# CoolantMonitor_MainBoard.net
KiCad netlist of a schematic drawn in Altium Designer
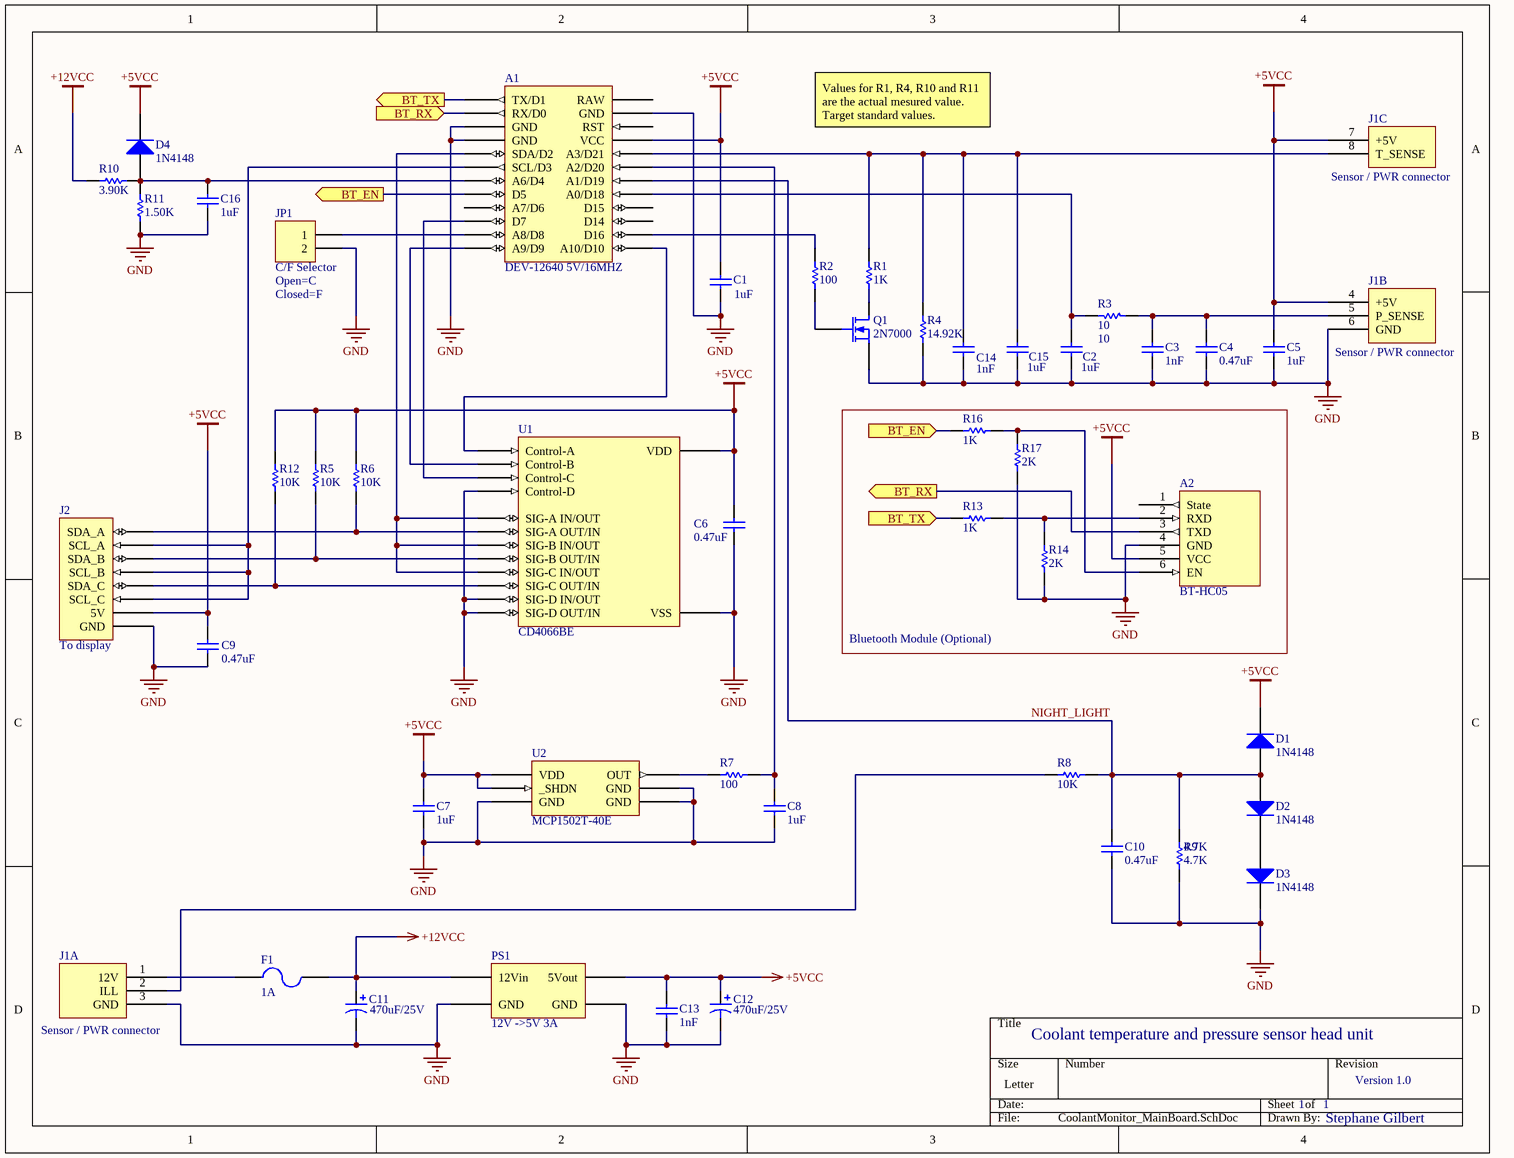
[diagram p0: CoolantMonitor_MainBoard.SchDoc]

(export (version "E")
  (design (tool "Eeschema 10.0.6"))
  (components
    (comp (ref "A1")
      (value "DEV-12640 5V/16MHZ")
      (footprint "ProMicro")
      (description "Arduino MCU")
      (fields (field (name "MANUFACTURER") "Sparkfun") (field (name "PART #") "DEV-12640"))
      (libsource (lib "CoolantMonitorLibrary") (part "ProMicro"))
    )
    (comp (ref "A2")
      (value "BT-HC05")
      (footprint "BT-HC05")
      (description "Bluetooth module")
      (fields (field (name "MANUFACTURER") "Many") (field (name "PART #") "HC-05"))
      (libsource (lib "CoolantMonitorLibrary") (part "BT-HC05"))
    )
    (comp (ref "C1")
      (value "1uF")
      (footprint "RAD_0.2_S")
      (description "Capacitor")
      (fields
        (field (name "MANUFACTURER") "TDK")
        (field (name "PART #") "FG28X7R1E105KRT06")
        (field (name "PUBLISHER") "Altium Limited")
      )
      (libsource (lib "Miscellaneous Devices") (part "Cap"))
    )
    (comp (ref "C2")
      (value "1uF")
      (footprint "RAD_0.2_S")
      (description "Capacitor")
      (fields
        (field (name "MANUFACTURER") "TDK")
        (field (name "PART #") "FG28X7R1E105KRT06")
        (field (name "PUBLISHER") "Altium Limited")
      )
      (libsource (lib "Miscellaneous Devices") (part "Cap"))
    )
    (comp (ref "C3")
      (value "1nF")
      (footprint "RAD_0.2_S")
      (description "Capacitor")
      (fields
        (field (name "MANUFACTURER") "Kemet")
        (field (name "PART #") "C315C102J3H5TA9170")
        (field (name "PUBLISHER") "Altium Limited")
      )
      (libsource (lib "Miscellaneous Devices") (part "Cap"))
    )
    (comp (ref "C4")
      (value "0.47uF")
      (footprint "RAD_0.2_S")
      (description "Capacitor")
      (fields
        (field (name "MANUFACTURER") "TDK")
        (field (name "PART #") "FA24X7R1E474KNU06")
        (field (name "PUBLISHER") "Altium Limited")
      )
      (libsource (lib "Miscellaneous Devices") (part "Cap"))
    )
    (comp (ref "C5")
      (value "1uF")
      (footprint "RAD_0.2_S")
      (description "Capacitor")
      (fields
        (field (name "MANUFACTURER") "TDK")
        (field (name "PART #") "FG28X7R1E105KRT06")
        (field (name "PUBLISHER") "Altium Limited")
      )
      (libsource (lib "Miscellaneous Devices") (part "Cap"))
    )
    (comp (ref "C6")
      (value "0.47uF")
      (footprint "RAD_0.2_S")
      (description "Capacitor")
      (fields
        (field (name "MANUFACTURER") "TDK")
        (field (name "PART #") "FA24X7R1E474KNU06")
        (field (name "PUBLISHER") "Altium Limited")
      )
      (libsource (lib "Miscellaneous Devices") (part "Cap"))
    )
    (comp (ref "C7")
      (value "1uF")
      (footprint "RAD_0.2_S")
      (description "Capacitor")
      (fields
        (field (name "MANUFACTURER") "TDK")
        (field (name "PART #") "FG28X7R1E105KRT06")
        (field (name "PUBLISHER") "Altium Limited")
      )
      (libsource (lib "Miscellaneous Devices") (part "Cap"))
    )
    (comp (ref "C8")
      (value "1uF")
      (footprint "RAD_0.2_S")
      (description "Capacitor")
      (fields
        (field (name "MANUFACTURER") "TDK")
        (field (name "PART #") "FG28X7R1E105KRT06")
        (field (name "PUBLISHER") "Altium Limited")
      )
      (libsource (lib "Miscellaneous Devices") (part "Cap"))
    )
    (comp (ref "C9")
      (value "0.47uF")
      (footprint "RAD_0.2_S")
      (description "Capacitor")
      (fields
        (field (name "MANUFACTURER") "TDK")
        (field (name "PART #") "FA24X7R1E474KNU06")
        (field (name "PUBLISHER") "Altium Limited")
      )
      (libsource (lib "Miscellaneous Devices") (part "Cap"))
    )
    (comp (ref "C10")
      (value "0.47uF")
      (footprint "RAD_0.2_S")
      (description "Capacitor")
      (fields
        (field (name "MANUFACTURER") "TDK")
        (field (name "PART #") "FA24X7R1E474KNU06")
        (field (name "PUBLISHER") "Altium Limited")
      )
      (libsource (lib "Miscellaneous Devices") (part "Cap"))
    )
    (comp (ref "C11")
      (value "470uF/25V")
      (footprint "RB_3.5MM")
      (description "Polarized Capacitor (Radial)")
      (fields
        (field (name "MANUFACTURER") "Vishay")
        (field (name "PART #") "MAL214656471E3")
        (field (name "PUBLISHER") "Altium Limited")
      )
      (libsource (lib "Miscellaneous Devices") (part "Cap Pol1"))
    )
    (comp (ref "C12")
      (value "470uF/25V")
      (footprint "RB_3.5MM")
      (description "Polarized Capacitor (Radial)")
      (fields
        (field (name "MANUFACTURER") "Vishay")
        (field (name "PART #") "MAL214656471E3")
        (field (name "PUBLISHER") "Altium Limited")
      )
      (libsource (lib "Miscellaneous Devices") (part "Cap Pol1"))
    )
    (comp (ref "C13")
      (value "1nF")
      (footprint "RAD_0.2_S")
      (description "Capacitor")
      (fields
        (field (name "MANUFACTURER") "Kemet")
        (field (name "PART #") "C315C102J3H5TA9170")
        (field (name "PUBLISHER") "Altium Limited")
      )
      (libsource (lib "Miscellaneous Devices") (part "Cap"))
    )
    (comp (ref "C14")
      (value "1nF")
      (footprint "RAD_0.2_S")
      (description "Capacitor")
      (fields
        (field (name "MANUFACTURER") "Kemet")
        (field (name "PART #") "C315C102J3H5TA9170")
        (field (name "PUBLISHER") "Altium Limited")
      )
      (libsource (lib "Miscellaneous Devices") (part "Cap"))
    )
    (comp (ref "C15")
      (value "1uF")
      (footprint "RAD_0.2_S")
      (description "Capacitor")
      (fields
        (field (name "MANUFACTURER") "TDK")
        (field (name "PART #") "FG28X7R1E105KRT06")
        (field (name "PUBLISHER") "Altium Limited")
      )
      (libsource (lib "Miscellaneous Devices") (part "Cap"))
    )
    (comp (ref "C16")
      (value "1uF")
      (footprint "RAD_0.2_S")
      (description "Capacitor")
      (fields
        (field (name "MANUFACTURER") "TDK")
        (field (name "PART #") "FG28X7R1E105KRT06")
        (field (name "PUBLISHER") "Altium Limited")
      )
      (libsource (lib "Miscellaneous Devices") (part "Cap"))
    )
    (comp (ref "D1")
      (value "1N4148")
      (footprint "DO-35A")
      (description "High Conductance Fast Diode")
      (fields (field (name "MANUFACTURER") "Onsemi") (field (name "PUBLISHER") "Altium Limited"))
      (libsource (lib "Miscellaneous Devices") (part "Diode 1N4148"))
    )
    (comp (ref "D2")
      (value "1N4148")
      (footprint "DO-35A")
      (description "High Conductance Fast Diode")
      (fields (field (name "MANUFACTURER") "Onsemi") (field (name "PUBLISHER") "Altium Limited"))
      (libsource (lib "Miscellaneous Devices") (part "Diode 1N4148"))
    )
    (comp (ref "D3")
      (value "1N4148")
      (footprint "DO-35A")
      (description "High Conductance Fast Diode")
      (fields (field (name "MANUFACTURER") "Onsemi") (field (name "PUBLISHER") "Altium Limited"))
      (libsource (lib "Miscellaneous Devices") (part "Diode 1N4148"))
    )
    (comp (ref "D4")
      (value "1N4148")
      (footprint "DO-35A")
      (description "High Conductance Fast Diode")
      (fields (field (name "MANUFACTURER") "Onsemi") (field (name "PUBLISHER") "Altium Limited"))
      (libsource (lib "Miscellaneous Devices") (part "Diode 1N4148"))
    )
    (comp (ref "F1")
      (value "1A")
      (footprint "AXIAL-0.4")
      (description "Fuse")
      (fields
        (field (name "MANUFACTURER") "Littlefuse")
        (field (name "PART #") "0251.500NRT1L")
        (field (name "PUBLISHER") "Altium Limited")
      )
      (libsource (lib "Miscellaneous Devices") (part "Fuse 2"))
    )
    (comp (ref "J1")
      (value "Sensor / PWR connector")
      (footprint "MTA-100-8")
      (description "8 Pins connector")
      (fields (field (name "MANUFACTURER") "Molex") (field (name "PART #") "1723162108"))
      (libsource (lib "CoolantMonitorLibrary") (part "SENS_INTERFACE_RX8"))
    )
    (comp (ref "J2")
      (value "To display")
      (footprint "MOLEX_ULTRA_FIT_8_POS_RA")
      (description "8 Pins connector")
      (fields (field (name "MANUFACTURER") "Molex") (field (name "PART #") "1723162108"))
      (libsource (lib "CoolantMonitorLibrary") (part "TRIPLE_DISPLAY_RX8"))
    )
    (comp (ref "JP1")
      (value "C/F Selector")
      (footprint "HDR1X2")
      (description "Header, 2-Pin")
      (fields (field (name "PUBLISHER") "Altium Limited"))
      (libsource (lib "Miscellaneous Connectors") (part "Header 2"))
    )
    (comp (ref "PS1")
      (value "12V ->5V 3A")
      (footprint "CPT_DC-DC")
      (description "CPT DC-DC 12V/5V 3A")
      (fields (field (name "MANUFACTURER") "Car Power Technology"))
      (libsource (lib "CoolantMonitorLibrary") (part "CPT_DC-DC"))
    )
    (comp (ref "Q1")
      (value "2N7000")
      (footprint "TO-92A")
      (description "N-Channel MOSFET")
      (fields (field (name "MANUFACTURER") "STMicroelectronics") (field (name "PUBLISHER") "Altium Limited"))
      (libsource (lib "Miscellaneous Devices") (part "MOSFET-N"))
    )
    (comp (ref "R1")
      (value "1K")
      (footprint "AXIAL-0.4")
      (description "Resistor")
      (fields
        (field (name "MANUFACTURER") "Stackpole Electronics Inc")
        (field (name "PART #") "CF18JT1K00")
        (field (name "PUBLISHER") "Altium Limited")
      )
      (libsource (lib "Miscellaneous Devices") (part "Res1"))
    )
    (comp (ref "R2")
      (value "100")
      (footprint "AXIAL-0.4")
      (description "Resistor")
      (fields
        (field (name "MANUFACTURER") "Stackpole Electronics Inc")
        (field (name "PART #") "CF18JT100R")
        (field (name "PUBLISHER") "Altium Limited")
      )
      (libsource (lib "Miscellaneous Devices") (part "Res1"))
    )
    (comp (ref "R3")
      (value "10")
      (footprint "AXIAL-0.4")
      (description "Resistor")
      (fields
        (field (name "ALTIUM_VALUE") "10")
        (field (name "MANUFACTURER") "Stackpole Electronics Inc")
        (field (name "PART #") "CF18JT10R0")
        (field (name "PUBLISHER") "Altium Limited")
      )
      (libsource (lib "Miscellaneous Devices") (part "Res1"))
    )
    (comp (ref "R4")
      (value "14.92K")
      (footprint "AXIAL-0.4")
      (description "Resistor")
      (fields
        (field (name "MANUFACTURER") "Stackpole Electronics Inc")
        (field (name "PART #") "CF18JT15K0")
        (field (name "PUBLISHER") "Altium Limited")
      )
      (libsource (lib "Miscellaneous Devices") (part "Res1"))
    )
    (comp (ref "R5")
      (value "10K")
      (footprint "AXIAL-0.4")
      (description "Resistor")
      (fields
        (field (name "MANUFACTURER") "Stackpole Electronics Inc")
        (field (name "PART #") "CF18JT10K0")
        (field (name "PUBLISHER") "Altium Limited")
      )
      (libsource (lib "Miscellaneous Devices") (part "Res1"))
    )
    (comp (ref "R6")
      (value "10K")
      (footprint "AXIAL-0.4")
      (description "Resistor")
      (fields
        (field (name "MANUFACTURER") "Stackpole Electronics Inc")
        (field (name "PART #") "CF18JT10K0")
        (field (name "PUBLISHER") "Altium Limited")
      )
      (libsource (lib "Miscellaneous Devices") (part "Res1"))
    )
    (comp (ref "R7")
      (value "100")
      (footprint "AXIAL-0.4")
      (description "Resistor")
      (fields
        (field (name "MANUFACTURER") "Stackpole Electronics Inc")
        (field (name "PART #") "CF18JT100R")
        (field (name "PUBLISHER") "Altium Limited")
      )
      (libsource (lib "Miscellaneous Devices") (part "Res1"))
    )
    (comp (ref "R8")
      (value "10K")
      (footprint "AXIAL-0.4")
      (description "Resistor")
      (fields
        (field (name "MANUFACTURER") "Stackpole Electronics Inc")
        (field (name "PART #") "CF18JT10K0")
        (field (name "PUBLISHER") "Altium Limited")
      )
      (libsource (lib "Miscellaneous Devices") (part "Res1"))
    )
    (comp (ref "R9")
      (value "4.7K")
      (footprint "AXIAL-0.4")
      (description "Resistor")
      (fields
        (field (name "ALTIUM_VALUE") "4.7K")
        (field (name "MANUFACTURER") "Stackpole Electronics Inc")
        (field (name "PART #") "CF18JT4K70")
        (field (name "PUBLISHER") "Altium Limited")
      )
      (libsource (lib "Miscellaneous Devices") (part "Res1"))
    )
    (comp (ref "R10")
      (value "3.90K")
      (footprint "AXIAL-0.4")
      (description "Resistor")
      (fields
        (field (name "MANUFACTURER") "Stackpole Electronics Inc")
        (field (name "PART #") "CF18JT3K90")
        (field (name "PUBLISHER") "Altium Limited")
      )
      (libsource (lib "Miscellaneous Devices") (part "Res1"))
    )
    (comp (ref "R11")
      (value "1.50K")
      (footprint "AXIAL-0.4")
      (description "Resistor")
      (fields
        (field (name "MANUFACTURER") "Stackpole Electronics Inc")
        (field (name "PART #") "CF18JT1K50")
        (field (name "PUBLISHER") "Altium Limited")
      )
      (libsource (lib "Miscellaneous Devices") (part "Res1"))
    )
    (comp (ref "R12")
      (value "10K")
      (footprint "AXIAL-0.4")
      (description "Resistor")
      (fields
        (field (name "MANUFACTURER") "Stackpole Electronics Inc")
        (field (name "PART #") "CF18JT10K0")
        (field (name "PUBLISHER") "Altium Limited")
      )
      (libsource (lib "Miscellaneous Devices") (part "Res1"))
    )
    (comp (ref "R13")
      (value "1K")
      (footprint "AXIAL-0.4")
      (description "Resistor")
      (fields
        (field (name "MANUFACTURER") "Stackpole Electronics Inc")
        (field (name "PART #") "CF18JT1K00")
        (field (name "PUBLISHER") "Altium Limited")
      )
      (libsource (lib "Miscellaneous Devices") (part "Res1"))
    )
    (comp (ref "R14")
      (value "2K")
      (footprint "AXIAL-0.4")
      (description "Resistor")
      (fields
        (field (name "MANUFACTURER") "Stackpole Electronics Inc")
        (field (name "PART #") "CF18JT2K00")
        (field (name "PUBLISHER") "Altium Limited")
      )
      (libsource (lib "Miscellaneous Devices") (part "Res1"))
    )
    (comp (ref "R16")
      (value "1K")
      (footprint "AXIAL-0.4")
      (description "Resistor")
      (fields
        (field (name "MANUFACTURER") "Stackpole Electronics Inc")
        (field (name "PART #") "CF18JT1K00")
        (field (name "PUBLISHER") "Altium Limited")
      )
      (libsource (lib "Miscellaneous Devices") (part "Res1"))
    )
    (comp (ref "R17")
      (value "2K")
      (footprint "AXIAL-0.4")
      (description "Resistor")
      (fields
        (field (name "MANUFACTURER") "Stackpole Electronics Inc")
        (field (name "PART #") "CF18JT2K00")
        (field (name "PUBLISHER") "Altium Limited")
      )
      (libsource (lib "Miscellaneous Devices") (part "Res1"))
    )
    (comp (ref "U1")
      (value "CD4066BE")
      (footprint "DIP-14")
      (description "Quad bilateral switch")
      (fields (field (name "MANUFACTURER") "TI"))
      (libsource (lib "CoolantMonitorLibrary") (part "CD4066BE"))
    )
    (comp (ref "U2")
      (value "MCP1502T-40E")
      (footprint "SOT-6-S")
      (description "Voltage reference")
      (fields (field (name "MANUFACTURER") "Michochip") (field (name "PART #") "MCP1502T-40E/CHY"))
      (libsource (lib "CoolantMonitorLibrary") (part "MCP1502"))
    )
  )
  (nets
    (net (code "1") (name "+5VCC") (class "Default")
      (node (ref "A1") (pin "21") (pinfunction "VCC_21") (pintype "power_in"))
      (node (ref "A2") (pin "5") (pinfunction "VCC_5") (pintype "power_in"))
      (node (ref "C1") (pin "2") (pinfunction "2_2") (pintype "passive"))
      (node (ref "C12") (pin "1") (pinfunction "1_1") (pintype "passive"))
      (node (ref "C13") (pin "2") (pinfunction "2_2") (pintype "passive"))
      (node (ref "C5") (pin "2") (pinfunction "2_2") (pintype "passive"))
      (node (ref "C6") (pin "2") (pinfunction "2_2") (pintype "passive"))
      (node (ref "C7") (pin "2") (pinfunction "2_2") (pintype "passive"))
      (node (ref "C9") (pin "2") (pinfunction "2_2") (pintype "passive"))
      (node (ref "D1") (pin "2") (pinfunction "K_2") (pintype "passive"))
      (node (ref "D4") (pin "2") (pinfunction "K_2") (pintype "passive"))
      (node (ref "J1") (pin "4") (pinfunction "+5V_4") (pintype "power_in"))
      (node (ref "J1") (pin "7") (pinfunction "+5V_7") (pintype "power_in"))
      (node (ref "J2") (pin "1") (pinfunction "5V_1") (pintype "power_in"))
      (node (ref "PS1") (pin "3") (pinfunction "5Vout_3") (pintype "power_in"))
      (node (ref "R12") (pin "2") (pinfunction "2_2") (pintype "passive"))
      (node (ref "R5") (pin "2") (pinfunction "2_2") (pintype "passive"))
      (node (ref "R6") (pin "2") (pinfunction "2_2") (pintype "passive"))
      (node (ref "U1") (pin "14") (pinfunction "VDD_14") (pintype "power_in"))
      (node (ref "U2") (pin "4") (pinfunction "_SHDN_4") (pintype "input"))
      (node (ref "U2") (pin "6") (pinfunction "VDD_6") (pintype "power_in"))
    )
    (net (code "2") (name "+12VCC") (class "Default")
      (node (ref "C11") (pin "1") (pinfunction "1_1") (pintype "passive"))
      (node (ref "F1") (pin "2") (pinfunction "2_2") (pintype "passive"))
      (node (ref "PS1") (pin "2") (pinfunction "12Vin_2") (pintype "power_in"))
      (node (ref "R10") (pin "1") (pinfunction "1_1") (pintype "passive"))
    )
    (net (code "3") (name "/BT_EN") (class "Default")
      (node (ref "A1") (pin "8") (pinfunction "D5_8") (pintype "bidirectional"))
      (node (ref "R16") (pin "2") (pinfunction "2_2") (pintype "passive"))
    )
    (net (code "4") (name "/BT_RX") (class "Default")
      (node (ref "A1") (pin "2") (pinfunction "RX/D0_2") (pintype "output"))
      (node (ref "A2") (pin "3") (pinfunction "TXD_3") (pintype "output"))
    )
    (net (code "5") (name "/BT_TX") (class "Default")
      (node (ref "A1") (pin "1") (pinfunction "TX/D1_1") (pintype "output"))
      (node (ref "R13") (pin "2") (pinfunction "2_2") (pintype "passive"))
    )
    (net (code "6") (name "/NIGHT_LIGHT") (class "Default")
      (node (ref "A1") (pin "18") (pinfunction "A1/D19_18") (pintype "input"))
      (node (ref "C10") (pin "2") (pinfunction "2_2") (pintype "passive"))
      (node (ref "D1") (pin "1") (pinfunction "A_1") (pintype "passive"))
      (node (ref "D2") (pin "1") (pinfunction "A_1") (pintype "passive"))
      (node (ref "R8") (pin "2") (pinfunction "2_2") (pintype "passive"))
      (node (ref "R9") (pin "2") (pinfunction "2_2") (pintype "passive"))
    )
    (net (code "7") (name "GND") (class "Default")
      (node (ref "A1") (pin "23") (pinfunction "GND_23") (pintype "power_in"))
      (node (ref "A1") (pin "3") (pinfunction "GND_3") (pintype "power_in"))
      (node (ref "A1") (pin "4") (pinfunction "GND_4") (pintype "power_in"))
      (node (ref "A2") (pin "4") (pinfunction "GND_4") (pintype "power_in"))
      (node (ref "C1") (pin "1") (pinfunction "1_1") (pintype "passive"))
      (node (ref "C10") (pin "1") (pinfunction "1_1") (pintype "passive"))
      (node (ref "C11") (pin "2") (pinfunction "2_2") (pintype "passive"))
      (node (ref "C12") (pin "2") (pinfunction "2_2") (pintype "passive"))
      (node (ref "C13") (pin "1") (pinfunction "1_1") (pintype "passive"))
      (node (ref "C14") (pin "1") (pinfunction "1_1") (pintype "passive"))
      (node (ref "C15") (pin "1") (pinfunction "1_1") (pintype "passive"))
      (node (ref "C16") (pin "1") (pinfunction "1_1") (pintype "passive"))
      (node (ref "C2") (pin "1") (pinfunction "1_1") (pintype "passive"))
      (node (ref "C3") (pin "1") (pinfunction "1_1") (pintype "passive"))
      (node (ref "C4") (pin "1") (pinfunction "1_1") (pintype "passive"))
      (node (ref "C5") (pin "1") (pinfunction "1_1") (pintype "passive"))
      (node (ref "C6") (pin "1") (pinfunction "1_1") (pintype "passive"))
      (node (ref "C7") (pin "1") (pinfunction "1_1") (pintype "passive"))
      (node (ref "C8") (pin "1") (pinfunction "1_1") (pintype "passive"))
      (node (ref "C9") (pin "1") (pinfunction "1_1") (pintype "passive"))
      (node (ref "D3") (pin "2") (pinfunction "K_2") (pintype "passive"))
      (node (ref "J1") (pin "3") (pinfunction "GND_3") (pintype "power_in"))
      (node (ref "J1") (pin "6") (pinfunction "GND_6") (pintype "power_in"))
      (node (ref "J2") (pin "2") (pinfunction "GND_2") (pintype "power_in"))
      (node (ref "JP1") (pin "2") (pinfunction "2_2") (pintype "passive"))
      (node (ref "PS1") (pin "1") (pinfunction "GND_1") (pintype "power_in"))
      (node (ref "PS1") (pin "4") (pinfunction "GND_4") (pintype "power_in"))
      (node (ref "Q1") (pin "3") (pinfunction "S_3") (pintype "passive"))
      (node (ref "R11") (pin "1") (pinfunction "1_1") (pintype "passive"))
      (node (ref "R14") (pin "2") (pinfunction "2_2") (pintype "passive"))
      (node (ref "R17") (pin "2") (pinfunction "2_2") (pintype "passive"))
      (node (ref "R4") (pin "1") (pinfunction "1_1") (pintype "passive"))
      (node (ref "R9") (pin "1") (pinfunction "1_1") (pintype "passive"))
      (node (ref "U1") (pin "10") (pinfunction "SIG-D_OUT/IN_10") (pintype "bidirectional"))
      (node (ref "U1") (pin "11") (pinfunction "SIG-D_IN/OUT_11") (pintype "bidirectional"))
      (node (ref "U1") (pin "12") (pinfunction "Control-D_12") (pintype "input"))
      (node (ref "U1") (pin "7") (pinfunction "VSS_7") (pintype "power_in"))
      (node (ref "U2") (pin "2") (pinfunction "GND_2") (pintype "power_in"))
      (node (ref "U2") (pin "3") (pinfunction "GND_3") (pintype "power_in"))
      (node (ref "U2") (pin "5") (pinfunction "GND_5") (pintype "power_in"))
    )
    (net (code "8") (name "Net-(A1-A0{slash}D18)") (class "Default")
      (node (ref "A1") (pin "17") (pinfunction "A0/D18_17") (pintype "input"))
      (node (ref "C2") (pin "2") (pinfunction "2_2") (pintype "passive"))
      (node (ref "R3") (pin "2") (pinfunction "2_2") (pintype "passive"))
    )
    (net (code "9") (name "Net-(A1-A2{slash}D20)") (class "Default")
      (node (ref "A1") (pin "19") (pinfunction "A2/D20_19") (pintype "input"))
      (node (ref "C8") (pin "2") (pinfunction "2_2") (pintype "passive"))
      (node (ref "R7") (pin "2") (pinfunction "2_2") (pintype "passive"))
    )
    (net (code "10") (name "Net-(A1-A3{slash}D21)") (class "Default")
      (node (ref "A1") (pin "20") (pinfunction "A3/D21_20") (pintype "input"))
      (node (ref "C14") (pin "2") (pinfunction "2_2") (pintype "passive"))
      (node (ref "C15") (pin "2") (pinfunction "2_2") (pintype "passive"))
      (node (ref "J1") (pin "8") (pinfunction "T_SENSE_8") (pintype "passive"))
      (node (ref "R1") (pin "2") (pinfunction "2_2") (pintype "passive"))
      (node (ref "R4") (pin "2") (pinfunction "2_2") (pintype "passive"))
    )
    (net (code "11") (name "Net-(A1-A6{slash}D4)") (class "Default")
      (node (ref "A1") (pin "7") (pinfunction "A6/D4_7") (pintype "bidirectional"))
      (node (ref "C16") (pin "2") (pinfunction "2_2") (pintype "passive"))
      (node (ref "D4") (pin "1") (pinfunction "A_1") (pintype "passive"))
      (node (ref "R10") (pin "2") (pinfunction "2_2") (pintype "passive"))
      (node (ref "R11") (pin "2") (pinfunction "2_2") (pintype "passive"))
    )
    (net (code "12") (name "Net-(A1-A8{slash}D8)") (class "Default")
      (node (ref "A1") (pin "11") (pinfunction "A8/D8_11") (pintype "bidirectional"))
      (node (ref "JP1") (pin "1") (pinfunction "1_1") (pintype "passive"))
    )
    (net (code "13") (name "Net-(A1-A9{slash}D9)") (class "Default")
      (node (ref "A1") (pin "12") (pinfunction "A9/D9_12") (pintype "bidirectional"))
      (node (ref "U1") (pin "5") (pinfunction "Control-B_5") (pintype "input"))
    )
    (net (code "14") (name "Net-(A1-A10{slash}D10)") (class "Default")
      (node (ref "A1") (pin "13") (pinfunction "A10/D10_13") (pintype "bidirectional"))
      (node (ref "U1") (pin "13") (pinfunction "Control-A_13") (pintype "input"))
    )
    (net (code "15") (name "Net-(A1-D7)") (class "Default")
      (node (ref "A1") (pin "10") (pinfunction "D7_10") (pintype "bidirectional"))
      (node (ref "U1") (pin "6") (pinfunction "Control-C_6") (pintype "input"))
    )
    (net (code "16") (name "Net-(A1-D16)") (class "Default")
      (node (ref "A1") (pin "14") (pinfunction "D16_14") (pintype "bidirectional"))
      (node (ref "R2") (pin "2") (pinfunction "2_2") (pintype "passive"))
    )
    (net (code "17") (name "Net-(A1-SCL{slash}D3)") (class "Default")
      (node (ref "A1") (pin "6") (pinfunction "SCL/D3_6") (pintype "output"))
      (node (ref "J2") (pin "4") (pinfunction "SCL_A_4") (pintype "input"))
      (node (ref "J2") (pin "6") (pinfunction "SCL_B_6") (pintype "input"))
      (node (ref "J2") (pin "8") (pinfunction "SCL_C_8") (pintype "input"))
    )
    (net (code "18") (name "Net-(A1-SDA{slash}D2)") (class "Default")
      (node (ref "A1") (pin "5") (pinfunction "SDA/D2_5") (pintype "bidirectional"))
      (node (ref "U1") (pin "1") (pinfunction "SIG-A_IN/OUT_1") (pintype "bidirectional"))
      (node (ref "U1") (pin "4") (pinfunction "SIG-B_IN/OUT_4") (pintype "bidirectional"))
      (node (ref "U1") (pin "8") (pinfunction "SIG-C_IN/OUT_8") (pintype "bidirectional"))
    )
    (net (code "19") (name "Net-(A2-EN)") (class "Default")
      (node (ref "A2") (pin "6") (pinfunction "EN_6") (pintype "input"))
      (node (ref "R16") (pin "1") (pinfunction "1_1") (pintype "passive"))
      (node (ref "R17") (pin "1") (pinfunction "1_1") (pintype "passive"))
    )
    (net (code "20") (name "Net-(A2-RXD)") (class "Default")
      (node (ref "A2") (pin "2") (pinfunction "RXD_2") (pintype "input"))
      (node (ref "R13") (pin "1") (pinfunction "1_1") (pintype "passive"))
      (node (ref "R14") (pin "1") (pinfunction "1_1") (pintype "passive"))
    )
    (net (code "21") (name "Net-(D2-K)") (class "Default")
      (node (ref "D2") (pin "2") (pinfunction "K_2") (pintype "passive"))
      (node (ref "D3") (pin "1") (pinfunction "A_1") (pintype "passive"))
    )
    (net (code "22") (name "Net-(J1A-12V)") (class "Default")
      (node (ref "F1") (pin "1") (pinfunction "1_1") (pintype "passive"))
      (node (ref "J1") (pin "1") (pinfunction "12V_1") (pintype "power_in"))
    )
    (net (code "23") (name "Net-(J1A-ILL)") (class "Default")
      (node (ref "J1") (pin "2") (pinfunction "ILL_2") (pintype "power_in"))
      (node (ref "R8") (pin "1") (pinfunction "1_1") (pintype "passive"))
    )
    (net (code "24") (name "Net-(J1B-P_SENSE)") (class "Default")
      (node (ref "C3") (pin "2") (pinfunction "2_2") (pintype "passive"))
      (node (ref "C4") (pin "2") (pinfunction "2_2") (pintype "passive"))
      (node (ref "J1") (pin "5") (pinfunction "P_SENSE_5") (pintype "power_in"))
      (node (ref "R3") (pin "1") (pinfunction "1_1") (pintype "passive"))
    )
    (net (code "25") (name "Net-(J2-SDA_A)") (class "Default")
      (node (ref "J2") (pin "3") (pinfunction "SDA_A_3") (pintype "bidirectional"))
      (node (ref "R6") (pin "1") (pinfunction "1_1") (pintype "passive"))
      (node (ref "U1") (pin "2") (pinfunction "SIG-A_OUT/IN_2") (pintype "bidirectional"))
    )
    (net (code "26") (name "Net-(J2-SDA_B)") (class "Default")
      (node (ref "J2") (pin "5") (pinfunction "SDA_B_5") (pintype "bidirectional"))
      (node (ref "R5") (pin "1") (pinfunction "1_1") (pintype "passive"))
      (node (ref "U1") (pin "3") (pinfunction "SIG-B_OUT/IN_3") (pintype "bidirectional"))
    )
    (net (code "27") (name "Net-(J2-SDA_C)") (class "Default")
      (node (ref "J2") (pin "7") (pinfunction "SDA_C_7") (pintype "bidirectional"))
      (node (ref "R12") (pin "1") (pinfunction "1_1") (pintype "passive"))
      (node (ref "U1") (pin "9") (pinfunction "SIG-C_OUT/IN_9") (pintype "bidirectional"))
    )
    (net (code "28") (name "Net-(Q1-D)") (class "Default")
      (node (ref "Q1") (pin "1") (pinfunction "D_1") (pintype "passive"))
      (node (ref "R1") (pin "1") (pinfunction "1_1") (pintype "passive"))
    )
    (net (code "29") (name "Net-(Q1-G)") (class "Default")
      (node (ref "Q1") (pin "2") (pinfunction "G_2") (pintype "passive"))
      (node (ref "R2") (pin "1") (pinfunction "1_1") (pintype "passive"))
    )
    (net (code "30") (name "Net-(U2-OUT)") (class "Default")
      (node (ref "R7") (pin "1") (pinfunction "1_1") (pintype "passive"))
      (node (ref "U2") (pin "1") (pinfunction "OUT_1") (pintype "output"))
    )
    (net (code "31") (name "unconnected-(A1-A7{slash}D6-Pad9)") (class "Default")
      (node (ref "A1") (pin "9") (pinfunction "A7/D6_9") (pintype "bidirectional"))
    )
    (net (code "32") (name "unconnected-(A1-D14-Pad15)") (class "Default")
      (node (ref "A1") (pin "15") (pinfunction "D14_15") (pintype "bidirectional"))
    )
    (net (code "33") (name "unconnected-(A1-D15-Pad16)") (class "Default")
      (node (ref "A1") (pin "16") (pinfunction "D15_16") (pintype "bidirectional"))
    )
    (net (code "34") (name "unconnected-(A1-RAW-Pad24)") (class "Default")
      (node (ref "A1") (pin "24") (pinfunction "RAW_24") (pintype "power_in"))
    )
    (net (code "35") (name "unconnected-(A1-RST-Pad22)") (class "Default")
      (node (ref "A1") (pin "22") (pinfunction "RST_22") (pintype "input"))
    )
    (net (code "36") (name "unconnected-(A2-State-Pad1)") (class "Default")
      (node (ref "A2") (pin "1") (pinfunction "State_1") (pintype "output"))
    )
  )
)
